# Sheet1.net
KiCad netlist of a schematic drawn in Altium Designer
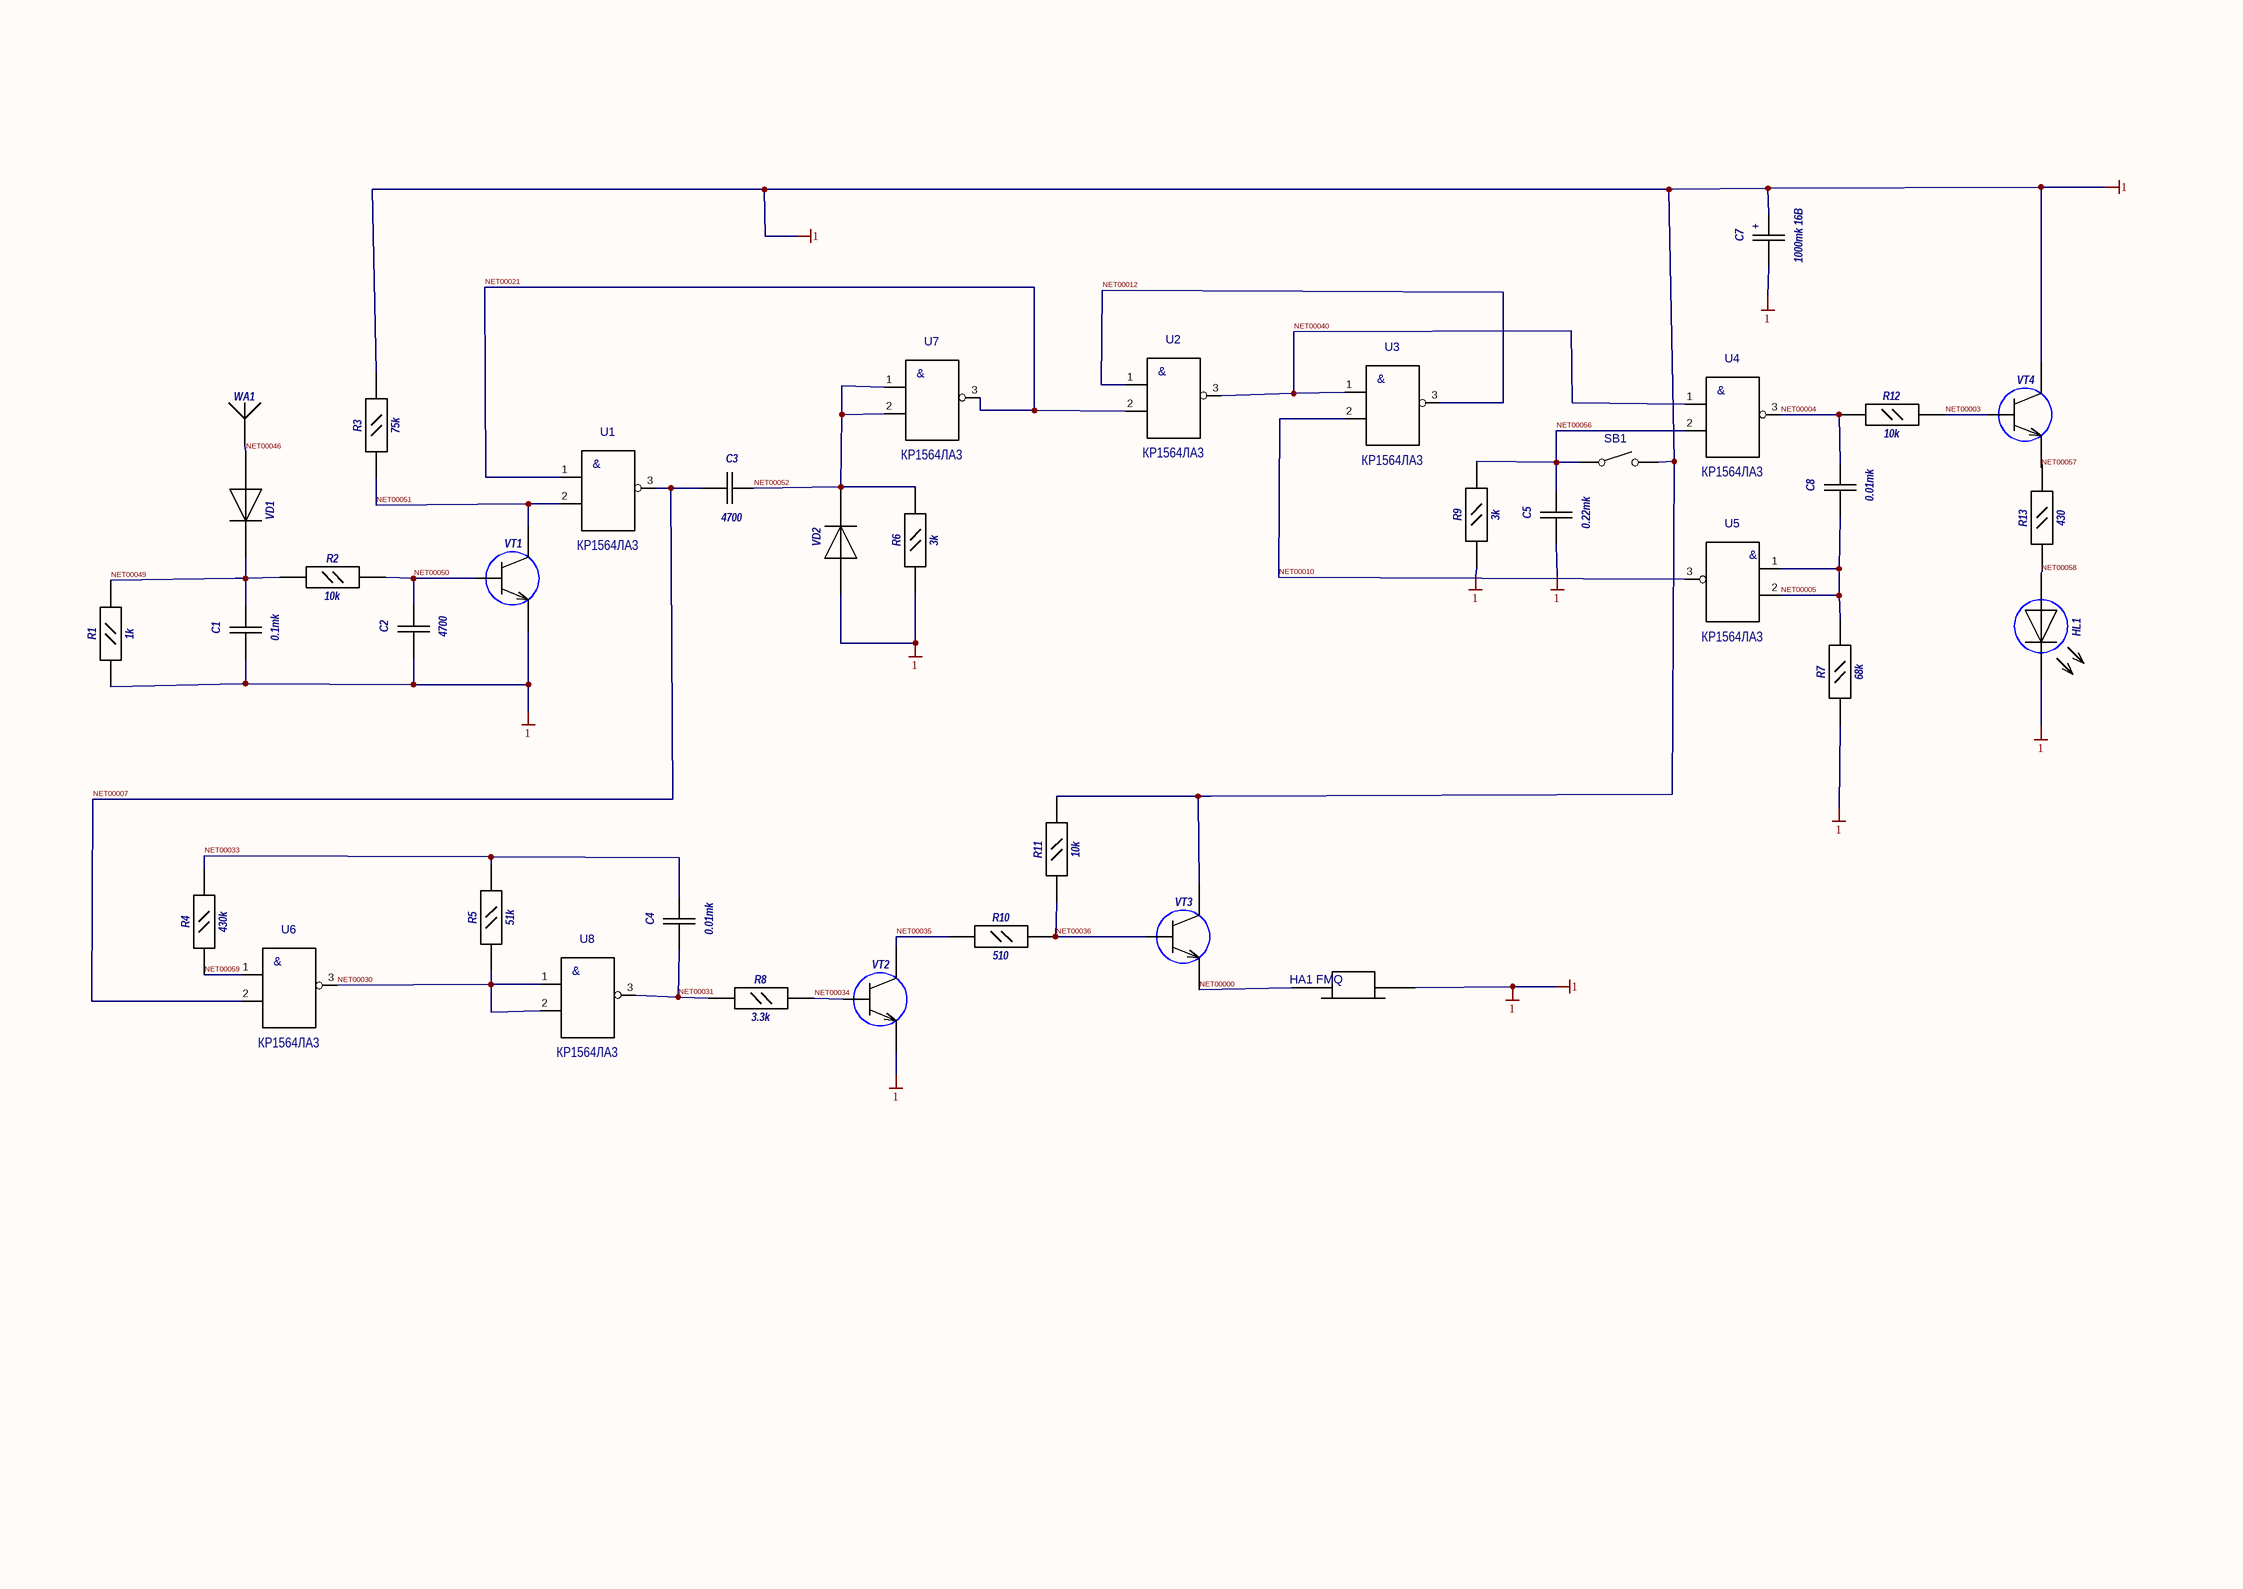
[diagram p0: Sheet1.SCHDOC]

(export (version "E")
  (design (tool "Eeschema 10.0.6"))
  (components
    (comp (ref "1")
      (value "HA1 FMQ")
      (footprint "ЗП-3")
      (description "ZP-3")
      (libsource (lib "*") (part "ZP-3"))
    )
    (comp (ref "C1")
      (value "0.1mk")
      (footprint "K71-6 (10X4)")
      (description "K71-6 (5-30 МК)")
      (libsource (lib "*") (part "K71-6 (5-30 МК)"))
    )
    (comp (ref "C2")
      (value "4700")
      (footprint "K71-6 (10X4)")
      (description "K71-6 (5-30 МК)")
      (libsource (lib "*") (part "K71-6 (5-30 МК)"))
    )
    (comp (ref "C3")
      (value "4700")
      (footprint "K71-6 (10X4)")
      (description "K71-6 (5-30 МК)")
      (libsource (lib "*") (part "K71-6 (5-30 МК)"))
    )
    (comp (ref "C4")
      (value "0.01mk")
      (footprint "K71-6 (10X4)")
      (description "K71-6 (5-30 МК)")
      (libsource (lib "*") (part "K71-6 (5-30 МК)"))
    )
    (comp (ref "C5")
      (value "0.22mk")
      (footprint "K71-6 (10X4)")
      (description "K71-6 (5-30 МК)")
      (libsource (lib "*") (part "K71-6 (5-30 МК)"))
    )
    (comp (ref "C7")
      (value "1000mk 16B")
      (footprint "К50-29 (17Х6)")
      (description "K50-29 (1;2,2;4,7;10;22 MK)")
      (libsource (lib "*") (part "K50-29 (1;2,2;4,7;10;22 MK)"))
    )
    (comp (ref "C8")
      (value "0.01mk")
      (footprint "K71-6 (10X4)")
      (description "K71-6 (5-30 МК)")
      (libsource (lib "*") (part "K71-6 (5-30 МК)"))
    )
    (comp (ref "HL1") (value "АЛ307") (footprint "АЛ307") (libsource (lib "*") (part "АЛ307")))
    (comp (ref "R1")
      (value "1k")
      (footprint "МЛТ(0.125)")
      (description "МЛТ(0.125)")
      (libsource (lib "*") (part "МЛТ(0.125)"))
    )
    (comp (ref "R2")
      (value "10k")
      (footprint "МЛТ(0.125)")
      (description "МЛТ(0.125)")
      (libsource (lib "*") (part "МЛТ(0.125)"))
    )
    (comp (ref "R3")
      (value "75k")
      (footprint "МЛТ(0.125)")
      (description "МЛТ(0.125)")
      (libsource (lib "*") (part "МЛТ(0.125)"))
    )
    (comp (ref "R4")
      (value "430k")
      (footprint "МЛТ(0.125)")
      (description "МЛТ(0.125)")
      (libsource (lib "*") (part "МЛТ(0.125)"))
    )
    (comp (ref "R5")
      (value "51k")
      (footprint "МЛТ(0.125)")
      (description "МЛТ(0.125)")
      (libsource (lib "*") (part "МЛТ(0.125)"))
    )
    (comp (ref "R6")
      (value "3k")
      (footprint "МЛТ(0.125)")
      (description "МЛТ(0.125)")
      (libsource (lib "*") (part "МЛТ(0.125)"))
    )
    (comp (ref "R7")
      (value "68k")
      (footprint "МЛТ(0.125)")
      (description "МЛТ(0.125)")
      (libsource (lib "*") (part "МЛТ(0.125)"))
    )
    (comp (ref "R8")
      (value "3.3k")
      (footprint "МЛТ(0.125)")
      (description "МЛТ(0.125)")
      (libsource (lib "*") (part "МЛТ(0.125)"))
    )
    (comp (ref "R9")
      (value "3k")
      (footprint "МЛТ(0.125)")
      (description "МЛТ(0.125)")
      (libsource (lib "*") (part "МЛТ(0.125)"))
    )
    (comp (ref "R10")
      (value "510")
      (footprint "МЛТ(0.125)")
      (description "МЛТ(0.125)")
      (libsource (lib "*") (part "МЛТ(0.125)"))
    )
    (comp (ref "R11")
      (value "10k")
      (footprint "МЛТ(0.125)")
      (description "МЛТ(0.125)")
      (libsource (lib "*") (part "МЛТ(0.125)"))
    )
    (comp (ref "R12")
      (value "10k")
      (footprint "МЛТ(0.125)")
      (description "МЛТ(0.125)")
      (libsource (lib "*") (part "МЛТ(0.125)"))
    )
    (comp (ref "R13")
      (value "430")
      (footprint "МЛТ(0.125)")
      (description "МЛТ(0.125)")
      (libsource (lib "*") (part "МЛТ(0.125)"))
    )
    (comp (ref "SB1") (value "TURN") (footprint "TRN") (libsource (lib "*") (part "TURN")))
    (comp (ref "U1") (value "КР1564ЛА3") (libsource (lib "*") (part "КР1564ЛА3")))
    (comp (ref "U2") (value "КР1564ЛА3") (libsource (lib "*") (part "КР1564ЛА3")))
    (comp (ref "U3") (value "КР1564ЛА3") (libsource (lib "*") (part "КР1564ЛА3")))
    (comp (ref "U4") (value "КР1564ЛА3") (libsource (lib "*") (part "КР1564ЛА3")))
    (comp (ref "U5") (value "КР1564ЛА3") (libsource (lib "*") (part "КР1564ЛА3")))
    (comp (ref "U6") (value "КР1564ЛА3") (libsource (lib "*") (part "КР1564ЛА3")))
    (comp (ref "U7") (value "КР1564ЛА3") (libsource (lib "*") (part "КР1564ЛА3")))
    (comp (ref "U8") (value "КР1564ЛА3") (libsource (lib "*") (part "КР1564ЛА3")))
    (comp (ref "VD1") (value "КД213А") (footprint "КД213") (libsource (lib "*") (part "КД213А")))
    (comp (ref "VD2") (value "КД213А") (footprint "КД213") (libsource (lib "*") (part "КД213А")))
    (comp (ref "VT1") (value "KT315") (footprint "КT315") (libsource (lib "*") (part "KT315")))
    (comp (ref "VT2") (value "KT315") (footprint "КT315") (libsource (lib "*") (part "KT315")))
    (comp (ref "VT3") (value "KT315") (footprint "КT315") (libsource (lib "*") (part "KT315")))
    (comp (ref "VT4") (value "KT315") (footprint "КT315") (libsource (lib "*") (part "KT315")))
    (comp (ref "WA1")
      (value "АНТЕННА(НЕСИММЕТРИЧНАЯ)")
      (footprint "АНТЕННА")
      (libsource (lib "*") (part "АНТЕННА(НЕСИММЕТРИЧНАЯ)"))
    )
  )
  (nets
    (net (code "1") (name "/NET00000") (class "Default")
      (node (ref "1") (pin "2") (pinfunction "2_2") (pintype "passive"))
      (node (ref "VT3") (pin "3") (pinfunction "3_3") (pintype "passive"))
    )
    (net (code "2") (name "/NET00003") (class "Default")
      (node (ref "R12") (pin "2") (pinfunction "2_2") (pintype "passive"))
      (node (ref "VT4") (pin "1") (pinfunction "1_1") (pintype "passive"))
    )
    (net (code "3") (name "/NET00004") (class "Default")
      (node (ref "C8") (pin "2") (pinfunction "2_2") (pintype "passive"))
      (node (ref "R12") (pin "1") (pinfunction "1_1") (pintype "passive"))
      (node (ref "U4") (pin "3") (pinfunction "3_3") (pintype "passive"))
    )
    (net (code "4") (name "/NET00005") (class "Default")
      (node (ref "C8") (pin "1") (pinfunction "1_1") (pintype "passive"))
      (node (ref "R7") (pin "2") (pinfunction "2_2") (pintype "passive"))
      (node (ref "U5") (pin "1") (pinfunction "1_1") (pintype "passive"))
      (node (ref "U5") (pin "2") (pinfunction "2_2") (pintype "passive"))
    )
    (net (code "5") (name "/NET00007") (class "Default")
      (node (ref "C3") (pin "1") (pinfunction "1_1") (pintype "passive"))
      (node (ref "U1") (pin "3") (pinfunction "3_3") (pintype "passive"))
      (node (ref "U6") (pin "2") (pinfunction "2_2") (pintype "passive"))
    )
    (net (code "6") (name "/NET00010") (class "Default")
      (node (ref "U3") (pin "2") (pinfunction "2_2") (pintype "passive"))
      (node (ref "U5") (pin "3") (pinfunction "3_3") (pintype "passive"))
    )
    (net (code "7") (name "/NET00012") (class "Default")
      (node (ref "U2") (pin "1") (pinfunction "1_1") (pintype "passive"))
      (node (ref "U3") (pin "3") (pinfunction "3_3") (pintype "passive"))
    )
    (net (code "8") (name "/NET00021") (class "Default")
      (node (ref "U1") (pin "1") (pinfunction "1_1") (pintype "passive"))
      (node (ref "U2") (pin "2") (pinfunction "2_2") (pintype "passive"))
      (node (ref "U7") (pin "3") (pinfunction "3_3") (pintype "passive"))
    )
    (net (code "9") (name "/NET00030") (class "Default")
      (node (ref "R5") (pin "1") (pinfunction "1_1") (pintype "passive"))
      (node (ref "U6") (pin "3") (pinfunction "3_3") (pintype "passive"))
      (node (ref "U8") (pin "1") (pinfunction "1_1") (pintype "passive"))
      (node (ref "U8") (pin "2") (pinfunction "2_2") (pintype "passive"))
    )
    (net (code "10") (name "/NET00031") (class "Default")
      (node (ref "C4") (pin "1") (pinfunction "1_1") (pintype "passive"))
      (node (ref "R8") (pin "1") (pinfunction "1_1") (pintype "passive"))
      (node (ref "U8") (pin "3") (pinfunction "3_3") (pintype "passive"))
    )
    (net (code "11") (name "/NET00033") (class "Default")
      (node (ref "C4") (pin "2") (pinfunction "2_2") (pintype "passive"))
      (node (ref "R4") (pin "2") (pinfunction "2_2") (pintype "passive"))
      (node (ref "R5") (pin "2") (pinfunction "2_2") (pintype "passive"))
    )
    (net (code "12") (name "/NET00034") (class "Default")
      (node (ref "R8") (pin "2") (pinfunction "2_2") (pintype "passive"))
      (node (ref "VT2") (pin "1") (pinfunction "1_1") (pintype "passive"))
    )
    (net (code "13") (name "/NET00035") (class "Default")
      (node (ref "R10") (pin "1") (pinfunction "1_1") (pintype "passive"))
      (node (ref "VT2") (pin "2") (pinfunction "2_2") (pintype "passive"))
    )
    (net (code "14") (name "/NET00036") (class "Default")
      (node (ref "R10") (pin "2") (pinfunction "2_2") (pintype "passive"))
      (node (ref "R11") (pin "1") (pinfunction "1_1") (pintype "passive"))
      (node (ref "VT3") (pin "1") (pinfunction "1_1") (pintype "passive"))
    )
    (net (code "15") (name "/NET00040") (class "Default")
      (node (ref "U2") (pin "3") (pinfunction "3_3") (pintype "passive"))
      (node (ref "U3") (pin "1") (pinfunction "1_1") (pintype "passive"))
      (node (ref "U4") (pin "1") (pinfunction "1_1") (pintype "passive"))
    )
    (net (code "16") (name "/NET00046") (class "Default")
      (node (ref "VD1") (pin "1") (pinfunction "1_1") (pintype "passive"))
      (node (ref "WA1") (pin "1") (pinfunction "1_1") (pintype "passive"))
    )
    (net (code "17") (name "/NET00049") (class "Default")
      (node (ref "C1") (pin "2") (pinfunction "2_2") (pintype "passive"))
      (node (ref "R1") (pin "1") (pinfunction "1_1") (pintype "passive"))
      (node (ref "R2") (pin "1") (pinfunction "1_1") (pintype "passive"))
      (node (ref "VD1") (pin "2") (pinfunction "2_2") (pintype "passive"))
    )
    (net (code "18") (name "/NET00050") (class "Default")
      (node (ref "C2") (pin "2") (pinfunction "2_2") (pintype "passive"))
      (node (ref "R2") (pin "2") (pinfunction "2_2") (pintype "passive"))
      (node (ref "VT1") (pin "1") (pinfunction "1_1") (pintype "passive"))
    )
    (net (code "19") (name "/NET00051") (class "Default")
      (node (ref "R3") (pin "1") (pinfunction "1_1") (pintype "passive"))
      (node (ref "U1") (pin "2") (pinfunction "2_2") (pintype "passive"))
      (node (ref "VT1") (pin "2") (pinfunction "2_2") (pintype "passive"))
    )
    (net (code "20") (name "/NET00052") (class "Default")
      (node (ref "C3") (pin "2") (pinfunction "2_2") (pintype "passive"))
      (node (ref "R6") (pin "2") (pinfunction "2_2") (pintype "passive"))
      (node (ref "U7") (pin "1") (pinfunction "1_1") (pintype "passive"))
      (node (ref "U7") (pin "2") (pinfunction "2_2") (pintype "passive"))
      (node (ref "VD2") (pin "2") (pinfunction "2_2") (pintype "passive"))
    )
    (net (code "21") (name "/NET00056") (class "Default")
      (node (ref "C5") (pin "2") (pinfunction "2_2") (pintype "passive"))
      (node (ref "R9") (pin "2") (pinfunction "2_2") (pintype "passive"))
      (node (ref "SB1") (pin "1") (pintype "passive"))
      (node (ref "U4") (pin "2") (pinfunction "2_2") (pintype "passive"))
    )
    (net (code "22") (name "/NET00057") (class "Default")
      (node (ref "R13") (pin "2") (pinfunction "2_2") (pintype "passive"))
      (node (ref "VT4") (pin "3") (pinfunction "3_3") (pintype "passive"))
    )
    (net (code "23") (name "/NET00058") (class "Default")
      (node (ref "HL1") (pin "1") (pinfunction "1_1") (pintype "passive"))
      (node (ref "R13") (pin "1") (pinfunction "1_1") (pintype "passive"))
    )
    (net (code "24") (name "/NET00059") (class "Default")
      (node (ref "R4") (pin "1") (pinfunction "1_1") (pintype "passive"))
      (node (ref "U6") (pin "1") (pinfunction "1_1") (pintype "passive"))
    )
    (net (code "25") (name "1") (class "Default")
      (node (ref "1") (pin "1") (pinfunction "1_1") (pintype "passive"))
      (node (ref "C1") (pin "1") (pinfunction "1_1") (pintype "passive"))
      (node (ref "C2") (pin "1") (pinfunction "1_1") (pintype "passive"))
      (node (ref "C5") (pin "1") (pinfunction "1_1") (pintype "passive"))
      (node (ref "C7") (pin "1") (pinfunction "1_1") (pintype "passive"))
      (node (ref "C7") (pin "2") (pinfunction "2_2") (pintype "passive"))
      (node (ref "HL1") (pin "2") (pinfunction "2_2") (pintype "passive"))
      (node (ref "R1") (pin "2") (pinfunction "2_2") (pintype "passive"))
      (node (ref "R11") (pin "2") (pinfunction "2_2") (pintype "passive"))
      (node (ref "R3") (pin "2") (pinfunction "2_2") (pintype "passive"))
      (node (ref "R6") (pin "1") (pinfunction "1_1") (pintype "passive"))
      (node (ref "R7") (pin "1") (pinfunction "1_1") (pintype "passive"))
      (node (ref "R9") (pin "1") (pinfunction "1_1") (pintype "passive"))
      (node (ref "SB1") (pin "2") (pintype "passive"))
      (node (ref "VD2") (pin "1") (pinfunction "1_1") (pintype "passive"))
      (node (ref "VT1") (pin "3") (pinfunction "3_3") (pintype "passive"))
      (node (ref "VT2") (pin "3") (pinfunction "3_3") (pintype "passive"))
      (node (ref "VT3") (pin "2") (pinfunction "2_2") (pintype "passive"))
      (node (ref "VT4") (pin "2") (pinfunction "2_2") (pintype "passive"))
    )
  )
)
